# LAN8720A.net
KiCad netlist of a schematic drawn in Altium Designer
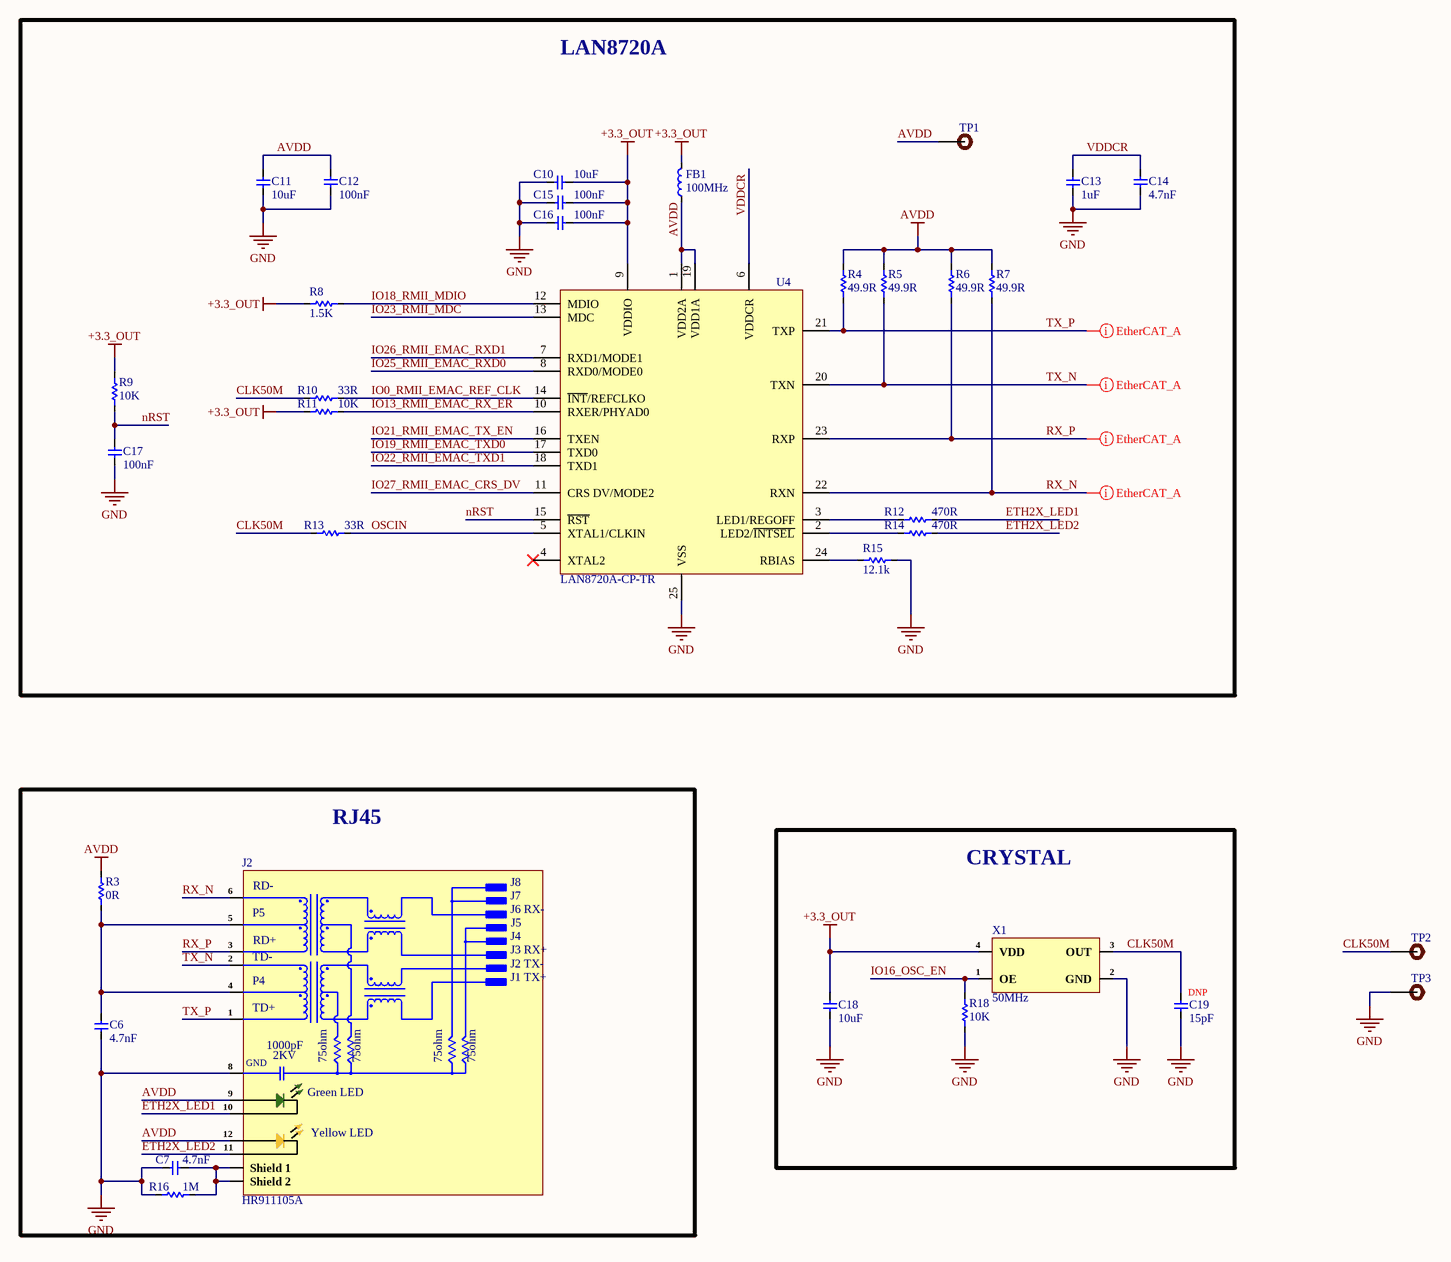
[diagram p0: LAN8720A.SchDoc]

(export (version "E")
  (design (tool "Eeschema 10.0.6"))
  (components
    (comp (ref "C6")
      (value "4.7nF")
      (footprint "Cap-0402")
      (description "CAP CER 4700PF 50V X7R 0402")
      (fields
        (field (name "MANUFACTURER") "Yageo")
        (field (name "MANUFACTURER PART NUMBER") "CC0402KRX7R9BB472")
      )
      (libsource (lib "eSpark Libraries") (part "CC0402KRX7R9BB472"))
    )
    (comp (ref "C7")
      (value "4.7nF")
      (footprint "Cap-1206")
      (description "CAP CER 4700PF 1KV X7R 1206")
      (fields
        (field (name "MANUFACTURER") "Yageo")
        (field (name "MANUFACTURER PART NUMBER") "CC1206KKX7RCBB472")
      )
      (libsource (lib "eSpark Libraries") (part "CC1206KKX7RCBB472"))
    )
    (comp (ref "C10")
      (value "10uF")
      (footprint "Cap-0603")
      (description "CAP CER 10UF 25V X5R 0603")
      (fields
        (field (name "MANUFACTURER") "Samsung")
        (field (name "MANUFACTURER PART NUMBER") "CL10A106MA8NRNC")
      )
      (libsource (lib "eSpark Libraries") (part "CL10A106MA8NRNC"))
    )
    (comp (ref "C11")
      (value "10uF")
      (footprint "Cap-0603")
      (description "CAP CER 10UF 25V X5R 0603")
      (fields
        (field (name "MANUFACTURER") "Samsung")
        (field (name "MANUFACTURER PART NUMBER") "CL10A106MA8NRNC")
      )
      (libsource (lib "eSpark Libraries") (part "CL10A106MA8NRNC"))
    )
    (comp (ref "C12")
      (value "100nF")
      (footprint "cap-0402")
      (description "CAP CER 0.1UF 50V X7R 0402")
      (fields
        (field (name "MANUFACTURER") "TDK")
        (field (name "MANUFACTURER PART NUMBER") "C1005X7R1H104KT000F")
      )
      (libsource (lib "eSpark Libraries") (part "C1005X7R1H104KT000F"))
    )
    (comp (ref "C13")
      (value "1uF")
      (footprint "Cap-0402")
      (description "CAP CER 1UF 16V X5R 0402")
      (fields
        (field (name "MANUFACTURER") "Yageo")
        (field (name "MANUFACTURER PART NUMBER") "CC0402KRX5R7BB105")
      )
      (libsource (lib "eSpark Libraries") (part "CC0402KRX5R7BB105"))
    )
    (comp (ref "C14")
      (value "4.7nF")
      (footprint "Cap-0402")
      (description "CAP CER 4700PF 50V X7R 0402")
      (fields
        (field (name "MANUFACTURER") "Yageo")
        (field (name "MANUFACTURER PART NUMBER") "CC0402KRX7R9BB472")
      )
      (libsource (lib "eSpark Libraries") (part "CC0402KRX7R9BB472"))
    )
    (comp (ref "C15")
      (value "100nF")
      (footprint "cap-0402")
      (description "CAP CER 0.1UF 50V X7R 0402")
      (fields
        (field (name "MANUFACTURER") "TDK")
        (field (name "MANUFACTURER PART NUMBER") "C1005X7R1H104KT000F")
      )
      (libsource (lib "eSpark Libraries") (part "C1005X7R1H104KT000F"))
    )
    (comp (ref "C16")
      (value "100nF")
      (footprint "cap-0402")
      (description "CAP CER 0.1UF 50V X7R 0402")
      (fields
        (field (name "MANUFACTURER") "TDK")
        (field (name "MANUFACTURER PART NUMBER") "C1005X7R1H104KT000F")
      )
      (libsource (lib "eSpark Libraries") (part "C1005X7R1H104KT000F"))
    )
    (comp (ref "C17")
      (value "100nF")
      (footprint "cap-0402")
      (description "CAP CER 0.1UF 50V X7R 0402")
      (fields
        (field (name "MANUFACTURER") "TDK")
        (field (name "MANUFACTURER PART NUMBER") "C1005X7R1H104KT000F")
      )
      (libsource (lib "eSpark Libraries") (part "C1005X7R1H104KT000F"))
    )
    (comp (ref "C18")
      (value "10uF")
      (footprint "Cap-0603")
      (description "CAP CER 10UF 25V X5R 0603")
      (fields
        (field (name "MANUFACTURER") "Samsung")
        (field (name "MANUFACTURER PART NUMBER") "CL10A106MA8NRNC")
      )
      (libsource (lib "eSpark Libraries") (part "CL10A106MA8NRNC"))
    )
    (comp (ref "C19")
      (value "15pF")
      (footprint "Cap-0603")
      (description "CAP CER 15PF 50V C0G/NPO 0603")
      (fields
        (field (name "MANUFACTURER") "Yageo")
        (field (name "MANUFACTURER PART NUMBER") "CC0603JRNPO9BN150")
      )
      (libsource (lib "eSpark Libraries") (part "CC0603JRNPO9BN150"))
    )
    (comp (ref "FB1")
      (value "100MHz")
      (footprint "IND-1206")
      (description "FERRITE BEAD 120 OHM 1206 1LN")
      (fields
        (field (name "MANUFACTURER") "Murata")
        (field (name "MANUFACTURER PART NUMBER") "BLM31PG121SN1L")
      )
      (libsource (lib "eSpark Libraries") (part "BLM31PG121SN1L"))
    )
    (comp (ref "J2")
      (value "HR911105A")
      (footprint "HR911105A")
      (description "RJ45 RJReceptacle 1 WithLED Plugin Ethernet Connectors/Modular Connectors (RJ45 RJ11) ROHS")
      (fields (field (name "MANUFACTURER") "HANRUN") (field (name "LCSC PART NUMBER") "C12074"))
      (libsource (lib "eSpark Libraries") (part "HR911105A"))
    )
    (comp (ref "R3")
      (value "0R")
      (footprint "Res-0402")
      (description "RES 0 OHM JUMPER 1/16W 0402")
      (fields
        (field (name "MANUFACTURER") "Yageo")
        (field (name "MANUFACTURER PART NUMBER") "RC0402FR-070RL")
      )
      (libsource (lib "eSpark Libraries") (part "RC0402FR-070RL"))
    )
    (comp (ref "R4")
      (value "49.9R")
      (footprint "Res-0402")
      (description "49.9Ω 62.5mW 50V ±100ppm/℃ Thick Film Resistor ±1% 0402 Chip Resistor - Surface Mount ROHS")
      (fields
        (field (name "MANUFACTURER") "YAGEO")
        (field (name "MANUFACTURER PART NUMBER") "RC0402FR-0749R9L")
      )
      (libsource (lib "eSpark Libraries") (part "RC0402FR-0749R9L"))
    )
    (comp (ref "R5")
      (value "49.9R")
      (footprint "Res-0402")
      (description "49.9Ω 62.5mW 50V ±100ppm/℃ Thick Film Resistor ±1% 0402 Chip Resistor - Surface Mount ROHS")
      (fields
        (field (name "MANUFACTURER") "YAGEO")
        (field (name "MANUFACTURER PART NUMBER") "RC0402FR-0749R9L")
      )
      (libsource (lib "eSpark Libraries") (part "RC0402FR-0749R9L"))
    )
    (comp (ref "R6")
      (value "49.9R")
      (footprint "Res-0402")
      (description "49.9Ω 62.5mW 50V ±100ppm/℃ Thick Film Resistor ±1% 0402 Chip Resistor - Surface Mount ROHS")
      (fields
        (field (name "MANUFACTURER") "YAGEO")
        (field (name "MANUFACTURER PART NUMBER") "RC0402FR-0749R9L")
      )
      (libsource (lib "eSpark Libraries") (part "RC0402FR-0749R9L"))
    )
    (comp (ref "R7")
      (value "49.9R")
      (footprint "Res-0402")
      (description "49.9Ω 62.5mW 50V ±100ppm/℃ Thick Film Resistor ±1% 0402 Chip Resistor - Surface Mount ROHS")
      (fields
        (field (name "MANUFACTURER") "YAGEO")
        (field (name "MANUFACTURER PART NUMBER") "RC0402FR-0749R9L")
      )
      (libsource (lib "eSpark Libraries") (part "RC0402FR-0749R9L"))
    )
    (comp (ref "R8")
      (value "1.5K")
      (footprint "Res-0402")
      (description "RES 1.5K OHM 1% 1/16W 0402")
      (fields
        (field (name "MANUFACTURER") "Yageo")
        (field (name "MANUFACTURER PART NUMBER") "RC0402FR-071K5L")
      )
      (libsource (lib "eSpark Libraries") (part "RC0402FR-071K5L"))
    )
    (comp (ref "R9")
      (value "10K")
      (footprint "Res-0402")
      (description "RES 10K OHM 1% 1/16W 0402")
      (fields
        (field (name "MANUFACTURER") "Yageo")
        (field (name "MANUFACTURER PART NUMBER") "RC0402FR-0710KL")
      )
      (libsource (lib "eSpark Libraries") (part "RC0402FR-0710KL"))
    )
    (comp (ref "R10")
      (value "33R")
      (footprint "Res-0402")
      (description "RES 33 OHM 1% 1/16W 0402")
      (fields
        (field (name "MANUFACTURER") "Yageo")
        (field (name "MANUFACTURER PART NUMBER") "RC0402FR-0733RL")
      )
      (libsource (lib "eSpark Libraries") (part "RC0402FR-0733RL"))
    )
    (comp (ref "R11")
      (value "10K")
      (footprint "Res-0402")
      (description "RES 10K OHM 1% 1/16W 0402")
      (fields
        (field (name "MANUFACTURER") "Yageo")
        (field (name "MANUFACTURER PART NUMBER") "RC0402FR-0710KL")
      )
      (libsource (lib "eSpark Libraries") (part "RC0402FR-0710KL"))
    )
    (comp (ref "R12")
      (value "470R")
      (footprint "Res-0402")
      (description "RES 470 OHM 1% 1/16W 0402")
      (fields
        (field (name "MANUFACTURER") "Yageo")
        (field (name "MANUFACTURER PART NUMBER") "RC0402FR-07470RL")
      )
      (libsource (lib "eSpark Libraries") (part "RC0402FR-07470RL"))
    )
    (comp (ref "R13")
      (value "33R")
      (footprint "Res-0402")
      (description "RES 33 OHM 1% 1/16W 0402")
      (fields
        (field (name "MANUFACTURER") "Yageo")
        (field (name "MANUFACTURER PART NUMBER") "RC0402FR-0733RL")
      )
      (libsource (lib "eSpark Libraries") (part "RC0402FR-0733RL"))
    )
    (comp (ref "R14")
      (value "470R")
      (footprint "Res-0402")
      (description "RES 470 OHM 1% 1/16W 0402")
      (fields
        (field (name "MANUFACTURER") "Yageo")
        (field (name "MANUFACTURER PART NUMBER") "RC0402FR-07470RL")
      )
      (libsource (lib "eSpark Libraries") (part "RC0402FR-07470RL"))
    )
    (comp (ref "R15")
      (value "12.1k")
      (footprint "Res-0402")
      (description "RES SMD 12.1KOHM 0.1% 1/16W 0402")
      (fields
        (field (name "MANUFACTURER") "Yageo")
        (field (name "MANUFACTURER PART NUMBER") "RT0402BRD0712K1L")
      )
      (libsource (lib "eSpark Libraries") (part "RT0402BRD0712K1L"))
    )
    (comp (ref "R16")
      (value "1M")
      (footprint "Res-1206")
      (description "RES 1M OHM 1% 1/4W 1206")
      (fields
        (field (name "MANUFACTURER") "Yageo")
        (field (name "MANUFACTURER PART NUMBER") "RC1206FR-071ML")
      )
      (libsource (lib "eSpark Libraries") (part "RC1206FR-071ML"))
    )
    (comp (ref "R18")
      (value "10K")
      (footprint "Res-0402")
      (description "RES 10K OHM 1% 1/16W 0402")
      (fields
        (field (name "MANUFACTURER") "Yageo")
        (field (name "MANUFACTURER PART NUMBER") "RC0402FR-0710KL")
      )
      (libsource (lib "eSpark Libraries") (part "RC0402FR-0710KL"))
    )
    (comp (ref "TP1")
      (value "TEST POINT 0.5mm Dia")
      (footprint "Test-point - 0.5mm")
      (description "Test Point ON")
      (libsource (lib "eSpark Libraries") (part "TEST POINT 0.5mm Dia"))
    )
    (comp (ref "TP2")
      (value "TEST POINT 0.5mm Dia")
      (footprint "Test-point - 0.5mm")
      (description "Test Point ON")
      (libsource (lib "eSpark Libraries") (part "TEST POINT 0.5mm Dia"))
    )
    (comp (ref "TP3")
      (value "TEST POINT 0.5mm Dia")
      (footprint "Test-point - 0.5mm")
      (description "Test Point ON")
      (libsource (lib "eSpark Libraries") (part "TEST POINT 0.5mm Dia"))
    )
    (comp (ref "U4")
      (value "LAN8720A-CP-TR")
      (footprint "LAN8720A-CP-TR")
      (description "IC TRANSCEIVER FULL 2/2 24SQFN")
      (fields (field (name "MANUFACTURER") "MICROCHIP") (field (name "LCSC PART NUMBER") "C45223"))
      (libsource (lib "eSpark Libraries") (part "LAN8720A-CP-TR"))
    )
    (comp (ref "X1")
      (value "50MHz")
      (footprint "OT2EL4C4JI-111OLP-50M")
      (description "1.8V~3.3V ±10ppm ±20ppm CMOS 50MHz SMD3225-4P Crystal Oscillators ROHS")
      (fields
        (field (name "MANUFACTURER") "YXC Crystal Oscillators")
        (field (name "MANUFACTURER PART NUMBER") "OT2EL4C4JI-111OLP-50M")
      )
      (libsource (lib "eSpark Libraries") (part "OT2EL4C4JI-111OLP-50M"))
    )
  )
  (nets
    (net (code "1") (name "+3.3_OUT") (class "Default")
      (node (ref "C10") (pin "2") (pinfunction "2_2") (pintype "passive"))
      (node (ref "C15") (pin "1") (pinfunction "1_1") (pintype "passive"))
      (node (ref "C16") (pin "1") (pinfunction "1_1") (pintype "passive"))
      (node (ref "C18") (pin "2") (pinfunction "2_2") (pintype "passive"))
      (node (ref "FB1") (pin "2") (pinfunction "2_2") (pintype "passive"))
      (node (ref "R11") (pin "2") (pinfunction "2_2") (pintype "passive"))
      (node (ref "R8") (pin "2") (pinfunction "2_2") (pintype "passive"))
      (node (ref "R9") (pin "2") (pinfunction "2_2") (pintype "passive"))
      (node (ref "U4") (pin "9") (pinfunction "VDDIO_9") (pintype "passive"))
      (node (ref "X1") (pin "4") (pinfunction "VDD_4") (pintype "passive"))
    )
    (net (code "2") (name "/CLK50M") (class "Default")
      (node (ref "C19") (pin "2") (pinfunction "2_2") (pintype "passive"))
      (node (ref "R10") (pin "1") (pinfunction "1_1") (pintype "passive"))
      (node (ref "R13") (pin "1") (pinfunction "1_1") (pintype "passive"))
      (node (ref "TP2") (pin "1") (pinfunction "1_1") (pintype "passive"))
      (node (ref "X1") (pin "3") (pinfunction "OUT_3") (pintype "passive"))
    )
    (net (code "3") (name "/ETH2X_LED1") (class "Default")
      (node (ref "J2") (pin "10") (pinfunction "CATHODE_10") (pintype "passive"))
      (node (ref "R12") (pin "2") (pinfunction "2_2") (pintype "passive"))
    )
    (net (code "4") (name "/ETH2X_LED2") (class "Default")
      (node (ref "J2") (pin "11") (pinfunction "CATHODE_11") (pintype "passive"))
      (node (ref "R14") (pin "2") (pinfunction "2_2") (pintype "passive"))
    )
    (net (code "5") (name "/IO0_RMII_EMAC_REF_CLK") (class "Default")
      (node (ref "R10") (pin "2") (pinfunction "2_2") (pintype "passive"))
      (node (ref "U4") (pin "14") (pinfunction "~{INT}/REFCLKO_14") (pintype "passive"))
    )
    (net (code "6") (name "/IO13_RMII_EMAC_RX_ER") (class "Default")
      (node (ref "R11") (pin "1") (pinfunction "1_1") (pintype "passive"))
      (node (ref "U4") (pin "10") (pinfunction "RXER/PHYAD0_10") (pintype "passive"))
    )
    (net (code "7") (name "/IO16_OSC_EN") (class "Default")
      (node (ref "R18") (pin "1") (pinfunction "1_1") (pintype "passive"))
      (node (ref "X1") (pin "1") (pinfunction "OE_1") (pintype "passive"))
    )
    (net (code "8") (name "/IO18_RMII_MDIO") (class "Default")
      (node (ref "R8") (pin "1") (pinfunction "1_1") (pintype "passive"))
      (node (ref "U4") (pin "12") (pinfunction "MDIO_12") (pintype "passive"))
    )
    (net (code "9") (name "/IO19_RMII_EMAC_TXD0") (class "Default")
      (node (ref "U4") (pin "17") (pinfunction "TXD0_17") (pintype "passive"))
    )
    (net (code "10") (name "/IO21_RMII_EMAC_TX_EN") (class "Default")
      (node (ref "U4") (pin "16") (pinfunction "TXEN_16") (pintype "passive"))
    )
    (net (code "11") (name "/IO22_RMII_EMAC_TXD1") (class "Default")
      (node (ref "U4") (pin "18") (pinfunction "TXD1_18") (pintype "passive"))
    )
    (net (code "12") (name "/IO23_RMII_MDC") (class "Default")
      (node (ref "U4") (pin "13") (pinfunction "MDC_13") (pintype "passive"))
    )
    (net (code "13") (name "/IO25_RMII_EMAC_RXD0") (class "Default")
      (node (ref "U4") (pin "8") (pinfunction "RXD0/MODE0_8") (pintype "passive"))
    )
    (net (code "14") (name "/IO26_RMII_EMAC_RXD1") (class "Default")
      (node (ref "U4") (pin "7") (pinfunction "RXD1/MODE1_7") (pintype "passive"))
    )
    (net (code "15") (name "/IO27_RMII_EMAC_CRS_DV") (class "Default")
      (node (ref "U4") (pin "11") (pinfunction "CRS_DV/MODE2_11") (pintype "passive"))
    )
    (net (code "16") (name "/OSCIN") (class "Default")
      (node (ref "R13") (pin "2") (pinfunction "2_2") (pintype "passive"))
      (node (ref "U4") (pin "5") (pinfunction "XTAL1/CLKIN_5") (pintype "passive"))
    )
    (net (code "17") (name "/RX_N") (class "Default")
      (node (ref "J2") (pin "6") (pinfunction "RD-_6") (pintype "passive"))
      (node (ref "R7") (pin "1") (pinfunction "1_1") (pintype "passive"))
      (node (ref "U4") (pin "22") (pinfunction "RXN_22") (pintype "passive"))
    )
    (net (code "18") (name "/RX_P") (class "Default")
      (node (ref "J2") (pin "3") (pinfunction "RD+_3") (pintype "passive"))
      (node (ref "R6") (pin "1") (pinfunction "1_1") (pintype "passive"))
      (node (ref "U4") (pin "23") (pinfunction "RXP_23") (pintype "passive"))
    )
    (net (code "19") (name "/TX_N") (class "Default")
      (node (ref "J2") (pin "2") (pinfunction "TD-_2") (pintype "passive"))
      (node (ref "R5") (pin "1") (pinfunction "1_1") (pintype "passive"))
      (node (ref "U4") (pin "20") (pinfunction "TXN_20") (pintype "passive"))
    )
    (net (code "20") (name "/TX_P") (class "Default")
      (node (ref "J2") (pin "1") (pinfunction "TD+_1") (pintype "passive"))
      (node (ref "R4") (pin "1") (pinfunction "1_1") (pintype "passive"))
      (node (ref "U4") (pin "21") (pinfunction "TXP_21") (pintype "passive"))
    )
    (net (code "21") (name "/VDDCR") (class "Default")
      (node (ref "C13") (pin "2") (pinfunction "2_2") (pintype "passive"))
      (node (ref "C14") (pin "1") (pinfunction "1_1") (pintype "passive"))
      (node (ref "U4") (pin "6") (pinfunction "VDDCR_6") (pintype "passive"))
    )
    (net (code "22") (name "/nRST") (class "Default")
      (node (ref "C17") (pin "2") (pinfunction "2_2") (pintype "passive"))
      (node (ref "R9") (pin "1") (pinfunction "1_1") (pintype "passive"))
      (node (ref "U4") (pin "15") (pinfunction "~{RST}_15") (pintype "passive"))
    )
    (net (code "23") (name "AVDD") (class "Default")
      (node (ref "C11") (pin "2") (pinfunction "2_2") (pintype "passive"))
      (node (ref "C12") (pin "1") (pinfunction "1_1") (pintype "passive"))
      (node (ref "FB1") (pin "1") (pinfunction "1_1") (pintype "passive"))
      (node (ref "J2") (pin "12") (pinfunction "ANODE_12") (pintype "passive"))
      (node (ref "J2") (pin "9") (pinfunction "ANODE_9") (pintype "passive"))
      (node (ref "R3") (pin "2") (pinfunction "2_2") (pintype "passive"))
      (node (ref "R4") (pin "2") (pinfunction "2_2") (pintype "passive"))
      (node (ref "R5") (pin "2") (pinfunction "2_2") (pintype "passive"))
      (node (ref "R6") (pin "2") (pinfunction "2_2") (pintype "passive"))
      (node (ref "R7") (pin "2") (pinfunction "2_2") (pintype "passive"))
      (node (ref "TP1") (pin "1") (pinfunction "1_1") (pintype "passive"))
      (node (ref "U4") (pin "1") (pinfunction "VDD2A_1") (pintype "passive"))
      (node (ref "U4") (pin "19") (pinfunction "VDD1A_19") (pintype "passive"))
    )
    (net (code "24") (name "GND") (class "Default")
      (node (ref "C10") (pin "1") (pinfunction "1_1") (pintype "passive"))
      (node (ref "C11") (pin "1") (pinfunction "1_1") (pintype "passive"))
      (node (ref "C12") (pin "2") (pinfunction "2_2") (pintype "passive"))
      (node (ref "C13") (pin "1") (pinfunction "1_1") (pintype "passive"))
      (node (ref "C14") (pin "2") (pinfunction "2_2") (pintype "passive"))
      (node (ref "C15") (pin "2") (pinfunction "2_2") (pintype "passive"))
      (node (ref "C16") (pin "2") (pinfunction "2_2") (pintype "passive"))
      (node (ref "C17") (pin "1") (pinfunction "1_1") (pintype "passive"))
      (node (ref "C18") (pin "1") (pinfunction "1_1") (pintype "passive"))
      (node (ref "C19") (pin "1") (pinfunction "1_1") (pintype "passive"))
      (node (ref "C6") (pin "1") (pinfunction "1_1") (pintype "passive"))
      (node (ref "C7") (pin "1") (pinfunction "1_1") (pintype "passive"))
      (node (ref "J2") (pin "8") (pinfunction "GND_8") (pintype "power_in"))
      (node (ref "R15") (pin "1") (pinfunction "1_1") (pintype "passive"))
      (node (ref "R16") (pin "1") (pinfunction "1_1") (pintype "passive"))
      (node (ref "R18") (pin "2") (pinfunction "2_2") (pintype "passive"))
      (node (ref "TP3") (pin "1") (pinfunction "1_1") (pintype "passive"))
      (node (ref "U4") (pin "25") (pinfunction "VSS_25") (pintype "passive"))
      (node (ref "X1") (pin "2") (pinfunction "GND_2") (pintype "passive"))
    )
    (net (code "25") (name "Net-(C7-Pad2)") (class "Default")
      (node (ref "C7") (pin "2") (pinfunction "2_2") (pintype "passive"))
      (node (ref "J2") (pin "Shield_1") (pinfunction "Shield_1_Shield_1") (pintype "passive"))
      (node (ref "J2") (pin "Shield_2") (pinfunction "Shield_2_Shield_2") (pintype "passive"))
      (node (ref "R16") (pin "2") (pinfunction "2_2") (pintype "passive"))
    )
    (net (code "26") (name "Net-(J2-P4)") (class "Default")
      (node (ref "C6") (pin "2") (pinfunction "2_2") (pintype "passive"))
      (node (ref "J2") (pin "4") (pinfunction "P4_4") (pintype "passive"))
      (node (ref "J2") (pin "5") (pinfunction "P5_5") (pintype "passive"))
      (node (ref "R3") (pin "1") (pinfunction "1_1") (pintype "passive"))
    )
    (net (code "27") (name "Net-(U4-LED1{slash}REGOFF)") (class "Default")
      (node (ref "R12") (pin "1") (pinfunction "1_1") (pintype "passive"))
      (node (ref "U4") (pin "3") (pinfunction "LED1/REGOFF_3") (pintype "passive"))
    )
    (net (code "28") (name "Net-(U4-LED2{slash}~{INTSEL})") (class "Default")
      (node (ref "R14") (pin "1") (pinfunction "1_1") (pintype "passive"))
      (node (ref "U4") (pin "2") (pinfunction "LED2/~{INTSEL}_2") (pintype "passive"))
    )
    (net (code "29") (name "Net-(U4-RBIAS)") (class "Default")
      (node (ref "R15") (pin "2") (pinfunction "2_2") (pintype "passive"))
      (node (ref "U4") (pin "24") (pinfunction "RBIAS_24") (pintype "passive"))
    )
    (net (code "30") (name "unconnected-(U4-XTAL2-Pad4)") (class "Default")
      (node (ref "U4") (pin "4") (pinfunction "XTAL2_4") (pintype "passive+no_connect"))
    )
  )
)
